# design.net
KiCad netlist of a schematic drawn in Altium Designer
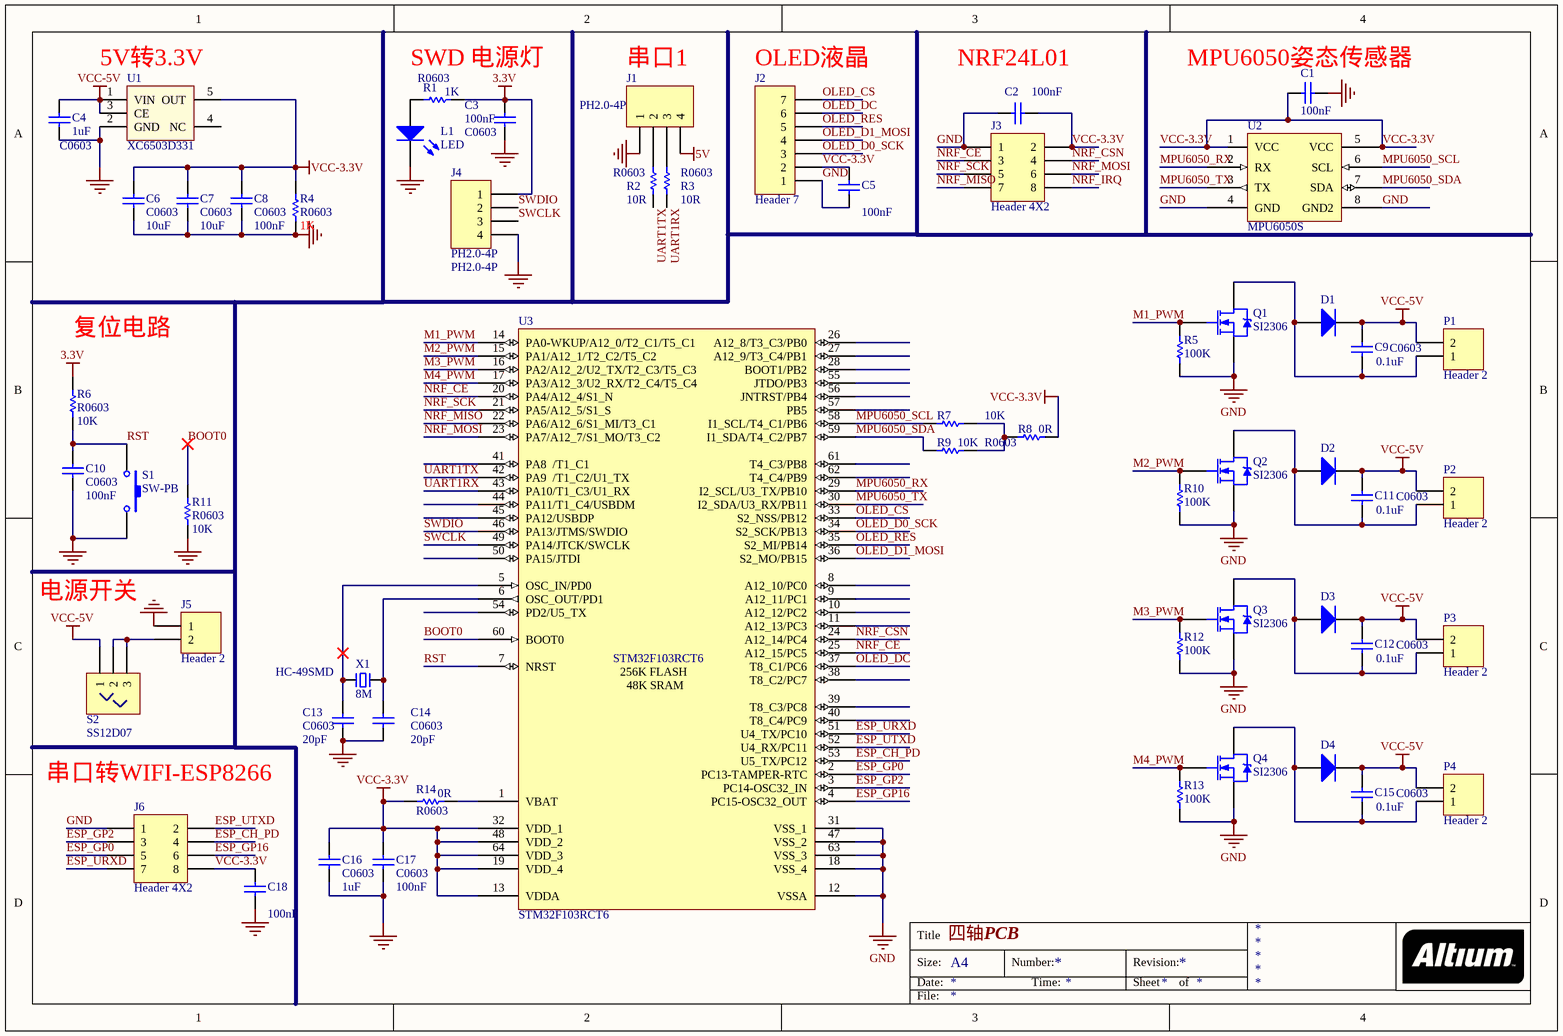
[diagram p0: 四轴.SchDoc]

(export (version "E")
  (design (tool "Eeschema 10.0.6"))
  (components
    (comp (ref "C1")
      (value "100nF")
      (footprint "LiyaoPCB库:0603")
      (description "Capacitor")
      (fields (field (name "Comment") "C0603") (field (name "PUBLISHER") "Altium Limited"))
      (libsource (lib "Miscellaneous Devices") (part "Cap"))
    )
    (comp (ref "C2")
      (value "100nF")
      (footprint "LiyaoPCB库:0603")
      (description "Capacitor")
      (fields (field (name "Comment") "C0603") (field (name "PUBLISHER") "Altium Limited"))
      (libsource (lib "Miscellaneous Devices") (part "Cap"))
    )
    (comp (ref "C3")
      (value "C0603")
      (footprint "0603")
      (description "Capacitor")
      (fields (field (name "ALTIUM_VALUE") "100nF") (field (name "PUBLISHER") "Altium Limited"))
      (libsource (lib "Miscellaneous Devices") (part "Cap"))
    )
    (comp (ref "C4")
      (value "C0603")
      (footprint "0603")
      (description "Capacitor")
      (fields (field (name "ALTIUM_VALUE") "1uF") (field (name "PUBLISHER") "Altium Limited"))
      (libsource (lib "Miscellaneous Devices") (part "Cap"))
    )
    (comp (ref "C5")
      (value "100nF")
      (footprint "LiyaoPCB库:0603")
      (description "Capacitor")
      (fields (field (name "Comment") "C0603") (field (name "PUBLISHER") "Altium Limited"))
      (libsource (lib "Miscellaneous Devices") (part "Cap"))
    )
    (comp (ref "C6")
      (value "C0603")
      (footprint "0603")
      (description "Capacitor")
      (fields (field (name "ALTIUM_VALUE") "10uF") (field (name "PUBLISHER") "Altium Limited"))
      (libsource (lib "Miscellaneous Devices") (part "Cap"))
    )
    (comp (ref "C7")
      (value "C0603")
      (footprint "0603")
      (description "Capacitor")
      (fields (field (name "ALTIUM_VALUE") "10uF") (field (name "PUBLISHER") "Altium Limited"))
      (libsource (lib "Miscellaneous Devices") (part "Cap"))
    )
    (comp (ref "C8")
      (value "C0603")
      (footprint "0603")
      (description "Capacitor")
      (fields (field (name "ALTIUM_VALUE") "100nF") (field (name "PUBLISHER") "Altium Limited"))
      (libsource (lib "Miscellaneous Devices") (part "Cap"))
    )
    (comp (ref "C9")
      (value "C0603")
      (footprint "0603")
      (description "Capacitor")
      (fields (field (name "ALTIUM_VALUE") "0.1uF") (field (name "PUBLISHER") "Altium Limited"))
      (libsource (lib "Miscellaneous Devices") (part "Cap"))
    )
    (comp (ref "C10")
      (value "C0603")
      (footprint "0603")
      (description "Capacitor")
      (fields (field (name "ALTIUM_VALUE") "100nF") (field (name "PUBLISHER") "Altium Limited"))
      (libsource (lib "Miscellaneous Devices") (part "Cap"))
    )
    (comp (ref "C11")
      (value "C0603")
      (footprint "0603")
      (description "Capacitor")
      (fields (field (name "ALTIUM_VALUE") "0.1uF") (field (name "PUBLISHER") "Altium Limited"))
      (libsource (lib "Miscellaneous Devices") (part "Cap"))
    )
    (comp (ref "C12")
      (value "C0603")
      (footprint "0603")
      (description "Capacitor")
      (fields (field (name "ALTIUM_VALUE") "0.1uF") (field (name "PUBLISHER") "Altium Limited"))
      (libsource (lib "Miscellaneous Devices") (part "Cap"))
    )
    (comp (ref "C13")
      (value "C0603")
      (footprint "0603")
      (description "Capacitor")
      (fields (field (name "ALTIUM_VALUE") "20pF") (field (name "PUBLISHER") "Altium Limited"))
      (libsource (lib "Miscellaneous Devices") (part "Cap"))
    )
    (comp (ref "C14")
      (value "C0603")
      (footprint "0603")
      (description "Capacitor")
      (fields (field (name "ALTIUM_VALUE") "20pF") (field (name "PUBLISHER") "Altium Limited"))
      (libsource (lib "Miscellaneous Devices") (part "Cap"))
    )
    (comp (ref "C15")
      (value "C0603")
      (footprint "0603")
      (description "Capacitor")
      (fields (field (name "ALTIUM_VALUE") "0.1uF") (field (name "PUBLISHER") "Altium Limited"))
      (libsource (lib "Miscellaneous Devices") (part "Cap"))
    )
    (comp (ref "C16")
      (value "C0603")
      (footprint "LiyaoPCB库:0603")
      (description "Capacitor")
      (fields (field (name "ALTIUM_VALUE") "1uF") (field (name "PUBLISHER") "Altium Limited"))
      (libsource (lib "Miscellaneous Devices") (part "Cap"))
    )
    (comp (ref "C17")
      (value "C0603")
      (footprint "LiyaoPCB库:0603")
      (description "Capacitor")
      (fields (field (name "ALTIUM_VALUE") "100nF") (field (name "PUBLISHER") "Altium Limited"))
      (libsource (lib "Miscellaneous Devices") (part "Cap"))
    )
    (comp (ref "C18")
      (value "100nF")
      (footprint "LiyaoPCB库:0603")
      (description "Capacitor")
      (fields (field (name "Comment") "C0603") (field (name "PUBLISHER") "Altium Limited"))
      (libsource (lib "Miscellaneous Devices") (part "Cap"))
    )
    (comp (ref "D1")
      (value "SS14")
      (footprint "LiyaoPCB库:SMA")
      (description "28V 1A")
      (fields (field (name "PUBLISHER") "Altium Limited"))
      (libsource (lib "Liyao原理图库") (part "SS14"))
    )
    (comp (ref "D2")
      (value "SS14")
      (footprint "LiyaoPCB库:SMA")
      (description "28V 1A")
      (fields (field (name "PUBLISHER") "Altium Limited"))
      (libsource (lib "Liyao原理图库") (part "SS14"))
    )
    (comp (ref "D3")
      (value "SS14")
      (footprint "LiyaoPCB库:SMA")
      (description "28V 1A")
      (fields (field (name "PUBLISHER") "Altium Limited"))
      (libsource (lib "Liyao原理图库") (part "SS14"))
    )
    (comp (ref "D4")
      (value "SS14")
      (footprint "LiyaoPCB库:SMA")
      (description "28V 1A")
      (fields (field (name "PUBLISHER") "Altium Limited"))
      (libsource (lib "Liyao原理图库") (part "SS14"))
    )
    (comp (ref "J1")
      (value "PH2.0-4P")
      (footprint "PH2.0-4P")
      (description "Header, 4-Pin")
      (fields (field (name "PUBLISHER") "Altium Limited"))
      (libsource (lib "Miscellaneous Connectors") (part "Header 4"))
    )
    (comp (ref "J2")
      (value "Header 7")
      (footprint "HDR1X7")
      (description "Header, 7-Pin")
      (fields (field (name "PUBLISHER") "Altium Limited"))
      (libsource (lib "Miscellaneous Connectors") (part "Header 7"))
    )
    (comp (ref "J3")
      (value "Header 4X2")
      (footprint "HDR2X4")
      (description "Header, 4-Pin, Dual row")
      (fields (field (name "PUBLISHER") "Altium Limited"))
      (libsource (lib "Miscellaneous Connectors") (part "Header 4X2"))
    )
    (comp (ref "J4")
      (value "PH2.0-4P")
      (footprint "PH2.0-4P")
      (description "Header, 4-Pin")
      (fields (field (name "ALTIUM_VALUE") "PH2.0-4P") (field (name "PUBLISHER") "Altium Limited"))
      (libsource (lib "") (part "Header 4_1"))
    )
    (comp (ref "J5")
      (value "Header 2")
      (footprint "XH2.54-2")
      (description "Header, 2-Pin")
      (fields (field (name "PUBLISHER") "Altium Limited"))
      (libsource (lib "") (part "Header 2_1"))
    )
    (comp (ref "J6")
      (value "Header 4X2")
      (footprint "HDR2X4")
      (description "Header, 4-Pin, Dual row")
      (fields (field (name "PUBLISHER") "Altium Limited"))
      (libsource (lib "Miscellaneous Connectors") (part "Header 4X2"))
    )
    (comp (ref "L1") (value "LED") (footprint "0603") (libsource (lib "Sparks") (part "LED")))
    (comp (ref "P1")
      (value "Header 2")
      (footprint "HDR1X2")
      (description "Header, 2-Pin")
      (fields (field (name "PUBLISHER") "Altium Limited"))
      (libsource (lib "Miscellaneous Connectors") (part "Header 2"))
    )
    (comp (ref "P2")
      (value "Header 2")
      (footprint "HDR1X2")
      (description "Header, 2-Pin")
      (fields (field (name "PUBLISHER") "Altium Limited"))
      (libsource (lib "Miscellaneous Connectors") (part "Header 2"))
    )
    (comp (ref "P3")
      (value "Header 2")
      (footprint "HDR1X2")
      (description "Header, 2-Pin")
      (fields (field (name "PUBLISHER") "Altium Limited"))
      (libsource (lib "Miscellaneous Connectors") (part "Header 2"))
    )
    (comp (ref "P4")
      (value "Header 2")
      (footprint "HDR1X2")
      (description "Header, 2-Pin")
      (fields (field (name "PUBLISHER") "Altium Limited"))
      (libsource (lib "Miscellaneous Connectors") (part "Header 2"))
    )
    (comp (ref "Q1")
      (value "SI2306")
      (footprint "LiyaoPCB库:SOT-23_L")
      (description "N-Channel MOSFET")
      (fields (field (name "PUBLISHER") "Altium Limited"))
      (libsource (lib "Liyao原理图库") (part "MOS-N"))
    )
    (comp (ref "Q2")
      (value "SI2306")
      (footprint "LiyaoPCB库:SOT-23_L")
      (description "N-Channel MOSFET")
      (fields (field (name "PUBLISHER") "Altium Limited"))
      (libsource (lib "Liyao原理图库") (part "MOS-N"))
    )
    (comp (ref "Q3")
      (value "SI2306")
      (footprint "LiyaoPCB库:SOT-23_L")
      (description "N-Channel MOSFET")
      (fields (field (name "PUBLISHER") "Altium Limited"))
      (libsource (lib "Liyao原理图库") (part "MOS-N"))
    )
    (comp (ref "Q4")
      (value "SI2306")
      (footprint "LiyaoPCB库:SOT-23_L")
      (description "N-Channel MOSFET")
      (fields (field (name "PUBLISHER") "Altium Limited"))
      (libsource (lib "Liyao原理图库") (part "MOS-N"))
    )
    (comp (ref "R1")
      (value "R0603")
      (footprint "0603")
      (description "Resistor")
      (fields (field (name "ALTIUM_VALUE") "1K") (field (name "PUBLISHER") "Altium Limited"))
      (libsource (lib "Miscellaneous Devices") (part "Res1"))
    )
    (comp (ref "R2")
      (value "R0603")
      (footprint "0603")
      (description "Resistor")
      (fields (field (name "ALTIUM_VALUE") "10R") (field (name "PUBLISHER") "Altium Limited"))
      (libsource (lib "Miscellaneous Devices") (part "Res1"))
    )
    (comp (ref "R3")
      (value "R0603")
      (footprint "0603")
      (description "Resistor")
      (fields (field (name "ALTIUM_VALUE") "10R") (field (name "PUBLISHER") "Altium Limited"))
      (libsource (lib "Miscellaneous Devices") (part "Res1"))
    )
    (comp (ref "R4")
      (value "R0603")
      (footprint "0603")
      (description "Resistor")
      (fields (field (name "ALTIUM_VALUE") "1K") (field (name "PUBLISHER") "Altium Limited"))
      (libsource (lib "Miscellaneous Devices") (part "Res1"))
    )
    (comp (ref "R5")
      (value "100K")
      (footprint "LiyaoPCB库:0603")
      (description "Resistor")
      (fields (field (name "Comment") "Res1") (field (name "PUBLISHER") "Altium Limited"))
      (libsource (lib "Miscellaneous Devices") (part "Res1"))
    )
    (comp (ref "R6")
      (value "R0603")
      (footprint "0603")
      (description "Resistor")
      (fields (field (name "ALTIUM_VALUE") "10K") (field (name "PUBLISHER") "Altium Limited"))
      (libsource (lib "Miscellaneous Devices") (part "Res1"))
    )
    (comp (ref "R7")
      (value "10K")
      (footprint "0603")
      (description "Resistor")
      (fields (field (name "PUBLISHER") "Altium Limited"))
      (libsource (lib "Miscellaneous Devices") (part "Res1"))
    )
    (comp (ref "R8")
      (value "0R")
      (footprint "0603")
      (description "Resistor")
      (fields (field (name "PUBLISHER") "Altium Limited"))
      (libsource (lib "Miscellaneous Devices") (part "Res1"))
    )
    (comp (ref "R9")
      (value "R0603")
      (footprint "0603")
      (description "Resistor")
      (fields (field (name "ALTIUM_VALUE") "10K") (field (name "PUBLISHER") "Altium Limited"))
      (libsource (lib "Miscellaneous Devices") (part "Res1"))
    )
    (comp (ref "R10")
      (value "100K")
      (footprint "LiyaoPCB库:0603")
      (description "Resistor")
      (fields (field (name "Comment") "Res1") (field (name "PUBLISHER") "Altium Limited"))
      (libsource (lib "Miscellaneous Devices") (part "Res1"))
    )
    (comp (ref "R11")
      (value "R0603")
      (footprint "0603")
      (description "Resistor")
      (fields (field (name "ALTIUM_VALUE") "10K") (field (name "PUBLISHER") "Altium Limited"))
      (libsource (lib "Miscellaneous Devices") (part "Res1"))
    )
    (comp (ref "R12")
      (value "100K")
      (footprint "LiyaoPCB库:0603")
      (description "Resistor")
      (fields (field (name "Comment") "Res1") (field (name "PUBLISHER") "Altium Limited"))
      (libsource (lib "Miscellaneous Devices") (part "Res1"))
    )
    (comp (ref "R13")
      (value "100K")
      (footprint "LiyaoPCB库:0603")
      (description "Resistor")
      (fields (field (name "Comment") "Res1") (field (name "PUBLISHER") "Altium Limited"))
      (libsource (lib "Miscellaneous Devices") (part "Res1"))
    )
    (comp (ref "R14")
      (value "R0603")
      (footprint "0603")
      (description "Resistor")
      (fields (field (name "ALTIUM_VALUE") "0R") (field (name "PUBLISHER") "Altium Limited"))
      (libsource (lib "Miscellaneous Devices") (part "Res1"))
    )
    (comp (ref "S1")
      (value "SW-PB")
      (footprint "SPST-2")
      (description "Switch")
      (fields (field (name "PUBLISHER") "Altium Limited"))
      (libsource (lib "Miscellaneous Devices") (part "SW-PB"))
    )
    (comp (ref "S2")
      (value "SS12D07")
      (footprint "LiyaoPCB库:SS-12D07")
      (libsource (lib "Liyao原理图库") (part "SS12D07"))
    )
    (comp (ref "U1")
      (value "XC6503D331")
      (footprint "SOT23-5")
      (libsource (lib "CYSchlib") (part "XC6503Dxxx"))
    )
    (comp (ref "U2")
      (value "MPU6050S")
      (footprint "LiyaoPCB库:MPU6050S")
      (libsource (lib "Liyao原理图库") (part "MPU6050S"))
    )
    (comp (ref "U3")
      (value "STM32F103RCT6")
      (footprint "LQFP64_N")
      (fields (field (name "PUBLISHER") "Altium Limited"))
      (libsource (lib "Liyao原理图库") (part "STM32F103RCT6"))
    )
    (comp (ref "X1")
      (value "8M")
      (footprint "HC-49SMD")
      (fields (field (name "ALTIUM_VALUE") "HC-49SMD"))
      (libsource (lib "CYSchlib") (part "XTAL"))
    )
  )
  (nets
    (net (code "1") (name "/BOOT0") (class "Default")
      (node (ref "R11") (pin "1") (pinfunction "1_1") (pintype "passive"))
      (node (ref "U3") (pin "60") (pinfunction "BOOT0_60") (pintype "input"))
    )
    (net (code "2") (name "/ESP_CH_PD") (class "Default")
      (node (ref "J6") (pin "4") (pinfunction "4_4") (pintype "passive"))
      (node (ref "U3") (pin "53") (pinfunction "U5_TX/PC12_53") (pintype "bidirectional"))
    )
    (net (code "3") (name "/ESP_GP0") (class "Default")
      (node (ref "J6") (pin "5") (pinfunction "5_5") (pintype "passive"))
      (node (ref "U3") (pin "2") (pinfunction "PC13-TAMPER-RTC_2") (pintype "bidirectional"))
    )
    (net (code "4") (name "/ESP_GP2") (class "Default")
      (node (ref "J6") (pin "3") (pinfunction "3_3") (pintype "passive"))
      (node (ref "U3") (pin "3") (pinfunction "PC14-OSC32_IN_3") (pintype "bidirectional"))
    )
    (net (code "5") (name "/ESP_GP16") (class "Default")
      (node (ref "J6") (pin "6") (pinfunction "6_6") (pintype "passive"))
      (node (ref "U3") (pin "4") (pinfunction "PC15-OSC32_OUT_4") (pintype "bidirectional"))
    )
    (net (code "6") (name "/ESP_URXD") (class "Default")
      (node (ref "J6") (pin "7") (pinfunction "7_7") (pintype "passive"))
      (node (ref "U3") (pin "51") (pinfunction "U4_TX/PC10_51") (pintype "bidirectional"))
    )
    (net (code "7") (name "/ESP_UTXD") (class "Default")
      (node (ref "J6") (pin "2") (pinfunction "2_2") (pintype "passive"))
      (node (ref "U3") (pin "52") (pinfunction "U4_RX/PC11_52") (pintype "bidirectional"))
    )
    (net (code "8") (name "/M1_PWM") (class "Default")
      (node (ref "Q1") (pin "1") (pinfunction "G_1") (pintype "passive"))
      (node (ref "R5") (pin "2") (pinfunction "2_2") (pintype "passive"))
      (node (ref "U3") (pin "14") (pinfunction "PA0-WKUP/A12_0/T2_C1/T5_C1_14") (pintype "bidirectional"))
    )
    (net (code "9") (name "/M2_PWM") (class "Default")
      (node (ref "Q2") (pin "1") (pinfunction "G_1") (pintype "passive"))
      (node (ref "R10") (pin "2") (pinfunction "2_2") (pintype "passive"))
      (node (ref "U3") (pin "15") (pinfunction "PA1/A12_1/T2_C2/T5_C2_15") (pintype "bidirectional"))
    )
    (net (code "10") (name "/M3_PWM") (class "Default")
      (node (ref "Q3") (pin "1") (pinfunction "G_1") (pintype "passive"))
      (node (ref "R12") (pin "2") (pinfunction "2_2") (pintype "passive"))
      (node (ref "U3") (pin "16") (pinfunction "PA2/A12_2/U2_TX/T2_C3/T5_C3_16") (pintype "bidirectional"))
    )
    (net (code "11") (name "/M4_PWM") (class "Default")
      (node (ref "Q4") (pin "1") (pinfunction "G_1") (pintype "passive"))
      (node (ref "R13") (pin "2") (pinfunction "2_2") (pintype "passive"))
      (node (ref "U3") (pin "17") (pinfunction "PA3/A12_3/U2_RX/T2_C4/T5_C4_17") (pintype "bidirectional"))
    )
    (net (code "12") (name "/MPU6050_RX") (class "Default")
      (node (ref "U2") (pin "2") (pinfunction "RX_2") (pintype "input"))
      (node (ref "U3") (pin "29") (pinfunction "I2_SCL/U3_TX/PB10_29") (pintype "bidirectional"))
    )
    (net (code "13") (name "/MPU6050_SCL") (class "Default")
      (node (ref "R7") (pin "1") (pinfunction "1_1") (pintype "passive"))
      (node (ref "U2") (pin "6") (pinfunction "SCL_6") (pintype "input"))
      (node (ref "U3") (pin "58") (pinfunction "I1_SCL/T4_C1/PB6_58") (pintype "bidirectional"))
    )
    (net (code "14") (name "/MPU6050_SDA") (class "Default")
      (node (ref "R9") (pin "1") (pinfunction "1_1") (pintype "passive"))
      (node (ref "U2") (pin "7") (pinfunction "SDA_7") (pintype "bidirectional"))
      (node (ref "U3") (pin "59") (pinfunction "I1_SDA/T4_C2/PB7_59") (pintype "bidirectional"))
    )
    (net (code "15") (name "/MPU6050_TX") (class "Default")
      (node (ref "U2") (pin "3") (pinfunction "TX_3") (pintype "output"))
      (node (ref "U3") (pin "30") (pinfunction "I2_SDA/U3_RX/PB11_30") (pintype "bidirectional"))
    )
    (net (code "16") (name "/NRF_CE") (class "Default")
      (node (ref "J3") (pin "3") (pinfunction "3_3") (pintype "passive"))
      (node (ref "U3") (pin "20") (pinfunction "PA4/A12_4/S1_N_20") (pintype "bidirectional"))
      (node (ref "U3") (pin "25") (pinfunction "A12_15/PC5_25") (pintype "bidirectional"))
    )
    (net (code "17") (name "/NRF_CSN") (class "Default")
      (node (ref "J3") (pin "4") (pinfunction "4_4") (pintype "passive"))
      (node (ref "U3") (pin "24") (pinfunction "A12_14/PC4_24") (pintype "bidirectional"))
    )
    (net (code "18") (name "/NRF_IRQ") (class "Default")
      (node (ref "J3") (pin "8") (pinfunction "8_8") (pintype "passive"))
    )
    (net (code "19") (name "/NRF_MISO") (class "Default")
      (node (ref "J3") (pin "7") (pinfunction "7_7") (pintype "passive"))
      (node (ref "U3") (pin "22") (pinfunction "PA6/A12_6/S1_MI/T3_C1_22") (pintype "bidirectional"))
    )
    (net (code "20") (name "/NRF_MOSI") (class "Default")
      (node (ref "J3") (pin "6") (pinfunction "6_6") (pintype "passive"))
      (node (ref "U3") (pin "23") (pinfunction "PA7/A12_7/S1_MO/T3_C2_23") (pintype "bidirectional"))
    )
    (net (code "21") (name "/NRF_SCK") (class "Default")
      (node (ref "J3") (pin "5") (pinfunction "5_5") (pintype "passive"))
      (node (ref "U3") (pin "21") (pinfunction "PA5/A12_5/S1_S_21") (pintype "bidirectional"))
    )
    (net (code "22") (name "/OLED_CS") (class "Default")
      (node (ref "J2") (pin "7") (pinfunction "7_7") (pintype "passive"))
      (node (ref "U3") (pin "33") (pinfunction "S2_NSS/PB12_33") (pintype "bidirectional"))
    )
    (net (code "23") (name "/OLED_D0_SCK") (class "Default")
      (node (ref "J2") (pin "3") (pinfunction "3_3") (pintype "passive"))
      (node (ref "U3") (pin "34") (pinfunction "S2_SCK/PB13_34") (pintype "bidirectional"))
    )
    (net (code "24") (name "/OLED_D1_MOSI") (class "Default")
      (node (ref "J2") (pin "4") (pinfunction "4_4") (pintype "passive"))
      (node (ref "U3") (pin "36") (pinfunction "S2_MO/PB15_36") (pintype "bidirectional"))
    )
    (net (code "25") (name "/OLED_DC") (class "Default")
      (node (ref "J2") (pin "6") (pinfunction "6_6") (pintype "passive"))
      (node (ref "U3") (pin "37") (pinfunction "T8_C1/PC6_37") (pintype "bidirectional"))
    )
    (net (code "26") (name "/OLED_RES") (class "Default")
      (node (ref "J2") (pin "5") (pinfunction "5_5") (pintype "passive"))
      (node (ref "U3") (pin "35") (pinfunction "S2_MI/PB14_35") (pintype "bidirectional"))
    )
    (net (code "27") (name "/RST") (class "Default")
      (node (ref "C10") (pin "1") (pinfunction "1_1") (pintype "passive"))
      (node (ref "R6") (pin "2") (pinfunction "2_2") (pintype "passive"))
      (node (ref "S1") (pin "1") (pinfunction "1_1") (pintype "passive"))
      (node (ref "U3") (pin "7") (pinfunction "NRST_7") (pintype "bidirectional"))
    )
    (net (code "28") (name "/SWCLK") (class "Default")
      (node (ref "J4") (pin "3") (pinfunction "3_3") (pintype "passive"))
      (node (ref "U3") (pin "49") (pinfunction "PA14/JTCK/SWCLK_49") (pintype "bidirectional"))
    )
    (net (code "29") (name "/SWDIO") (class "Default")
      (node (ref "J4") (pin "2") (pinfunction "2_2") (pintype "passive"))
      (node (ref "U3") (pin "46") (pinfunction "PA13/JTMS/SWDIO_46") (pintype "bidirectional"))
    )
    (net (code "30") (name "/UART1RX") (class "Default")
      (node (ref "R3") (pin "2") (pinfunction "2_2") (pintype "passive"))
      (node (ref "U3") (pin "43") (pinfunction "PA10/T1_C3/U1_RX_43") (pintype "bidirectional"))
    )
    (net (code "31") (name "/UART1TX") (class "Default")
      (node (ref "R2") (pin "2") (pinfunction "2_2") (pintype "passive"))
      (node (ref "U3") (pin "42") (pinfunction "PA9__/T1_C2/U1_TX_42") (pintype "bidirectional"))
    )
    (net (code "32") (name "3.3V") (class "Default")
      (node (ref "C3") (pin "1") (pinfunction "1_1") (pintype "passive"))
      (node (ref "J4") (pin "1") (pinfunction "1_1") (pintype "passive"))
      (node (ref "R1") (pin "2") (pinfunction "2_2") (pintype "passive"))
      (node (ref "R6") (pin "1") (pinfunction "1_1") (pintype "passive"))
    )
    (net (code "33") (name "5V") (class "Default")
      (node (ref "J1") (pin "4") (pinfunction "4_4") (pintype "passive"))
    )
    (net (code "34") (name "GND") (class "Default")
      (node (ref "C1") (pin "2") (pinfunction "2_2") (pintype "passive"))
      (node (ref "C10") (pin "2") (pinfunction "2_2") (pintype "passive"))
      (node (ref "C13") (pin "1") (pinfunction "1_1") (pintype "passive"))
      (node (ref "C14") (pin "1") (pinfunction "1_1") (pintype "passive"))
      (node (ref "C16") (pin "1") (pinfunction "1_1") (pintype "passive"))
      (node (ref "C17") (pin "1") (pinfunction "1_1") (pintype "passive"))
      (node (ref "C18") (pin "2") (pinfunction "2_2") (pintype "passive"))
      (node (ref "C2") (pin "2") (pinfunction "2_2") (pintype "passive"))
      (node (ref "C3") (pin "2") (pinfunction "2_2") (pintype "passive"))
      (node (ref "C4") (pin "1") (pinfunction "1_1") (pintype "passive"))
      (node (ref "C5") (pin "2") (pinfunction "2_2") (pintype "passive"))
      (node (ref "C6") (pin "2") (pinfunction "2_2") (pintype "passive"))
      (node (ref "C7") (pin "1") (pinfunction "1_1") (pintype "passive"))
      (node (ref "C8") (pin "1") (pinfunction "1_1") (pintype "passive"))
      (node (ref "J1") (pin "1") (pinfunction "1_1") (pintype "passive"))
      (node (ref "J2") (pin "1") (pinfunction "1_1") (pintype "passive"))
      (node (ref "J3") (pin "1") (pinfunction "1_1") (pintype "passive"))
      (node (ref "J4") (pin "4") (pinfunction "4_4") (pintype "passive"))
      (node (ref "J5") (pin "1") (pinfunction "1_1") (pintype "passive"))
      (node (ref "J6") (pin "1") (pinfunction "1_1") (pintype "passive"))
      (node (ref "L1") (pin "2") (pinfunction "K_2") (pintype "passive"))
      (node (ref "Q1") (pin "2") (pinfunction "S_2") (pintype "passive"))
      (node (ref "Q2") (pin "2") (pinfunction "S_2") (pintype "passive"))
      (node (ref "Q3") (pin "2") (pinfunction "S_2") (pintype "passive"))
      (node (ref "Q4") (pin "2") (pinfunction "S_2") (pintype "passive"))
      (node (ref "R10") (pin "1") (pinfunction "1_1") (pintype "passive"))
      (node (ref "R11") (pin "2") (pinfunction "2_2") (pintype "passive"))
      (node (ref "R12") (pin "1") (pinfunction "1_1") (pintype "passive"))
      (node (ref "R13") (pin "1") (pinfunction "1_1") (pintype "passive"))
      (node (ref "R4") (pin "1") (pinfunction "1_1") (pintype "passive"))
      (node (ref "R5") (pin "1") (pinfunction "1_1") (pintype "passive"))
      (node (ref "S1") (pin "2") (pinfunction "2_2") (pintype "passive"))
      (node (ref "U1") (pin "2") (pinfunction "GND_2") (pintype "passive"))
      (node (ref "U2") (pin "4") (pinfunction "GND_4") (pintype "power_in"))
      (node (ref "U2") (pin "8") (pinfunction "GND2_8") (pintype "passive"))
      (node (ref "U3") (pin "12") (pinfunction "VSSA_12") (pintype "power_in"))
      (node (ref "U3") (pin "18") (pinfunction "VSS_4_18") (pintype "power_in"))
      (node (ref "U3") (pin "31") (pinfunction "VSS_1_31") (pintype "power_in"))
      (node (ref "U3") (pin "47") (pinfunction "VSS_2_47") (pintype "power_in"))
      (node (ref "U3") (pin "63") (pinfunction "VSS_3_63") (pintype "power_in"))
    )
    (net (code "35") (name "Net-(D1-A)") (class "Default")
      (node (ref "C9") (pin "1") (pinfunction "1_1") (pintype "passive"))
      (node (ref "D1") (pin "1") (pinfunction "A_1") (pintype "passive"))
      (node (ref "P1") (pin "1") (pinfunction "1_1") (pintype "passive"))
      (node (ref "Q1") (pin "3") (pinfunction "D_3") (pintype "passive"))
    )
    (net (code "36") (name "Net-(D2-A)") (class "Default")
      (node (ref "C11") (pin "1") (pinfunction "1_1") (pintype "passive"))
      (node (ref "D2") (pin "1") (pinfunction "A_1") (pintype "passive"))
      (node (ref "P2") (pin "1") (pinfunction "1_1") (pintype "passive"))
      (node (ref "Q2") (pin "3") (pinfunction "D_3") (pintype "passive"))
    )
    (net (code "37") (name "Net-(D3-A)") (class "Default")
      (node (ref "C12") (pin "1") (pinfunction "1_1") (pintype "passive"))
      (node (ref "D3") (pin "1") (pinfunction "A_1") (pintype "passive"))
      (node (ref "P3") (pin "1") (pinfunction "1_1") (pintype "passive"))
      (node (ref "Q3") (pin "3") (pinfunction "D_3") (pintype "passive"))
    )
    (net (code "38") (name "Net-(D4-A)") (class "Default")
      (node (ref "C15") (pin "1") (pinfunction "1_1") (pintype "passive"))
      (node (ref "D4") (pin "1") (pinfunction "A_1") (pintype "passive"))
      (node (ref "P4") (pin "1") (pinfunction "1_1") (pintype "passive"))
      (node (ref "Q4") (pin "3") (pinfunction "D_3") (pintype "passive"))
    )
    (net (code "39") (name "Net-(J1-Pad2)") (class "Default")
      (node (ref "J1") (pin "2") (pinfunction "2_2") (pintype "passive"))
      (node (ref "R2") (pin "1") (pinfunction "1_1") (pintype "passive"))
    )
    (net (code "40") (name "Net-(J1-Pad3)") (class "Default")
      (node (ref "J1") (pin "3") (pinfunction "3_3") (pintype "passive"))
      (node (ref "R3") (pin "1") (pinfunction "1_1") (pintype "passive"))
    )
    (net (code "41") (name "Net-(J5-Pad2)") (class "Default")
      (node (ref "J5") (pin "2") (pinfunction "2_2") (pintype "passive"))
      (node (ref "S2") (pin "2") (pinfunction "2_2") (pintype "passive"))
      (node (ref "S2") (pin "3") (pinfunction "3_3") (pintype "passive"))
    )
    (net (code "42") (name "Net-(L1-A)") (class "Default")
      (node (ref "L1") (pin "1") (pinfunction "A_1") (pintype "passive"))
      (node (ref "R1") (pin "1") (pinfunction "1_1") (pintype "passive"))
    )
    (net (code "43") (name "Net-(R7-Pad2)") (class "Default")
      (node (ref "R7") (pin "2") (pinfunction "2_2") (pintype "passive"))
      (node (ref "R8") (pin "2") (pinfunction "2_2") (pintype "passive"))
      (node (ref "R9") (pin "2") (pinfunction "2_2") (pintype "passive"))
    )
    (net (code "44") (name "Net-(U3-OSC_IN{slash}PD0)") (class "Default")
      (node (ref "C13") (pin "2") (pinfunction "2_2") (pintype "passive"))
      (node (ref "U3") (pin "5") (pinfunction "OSC_IN/PD0_5") (pintype "input"))
      (node (ref "X1") (pin "2") (pinfunction "2_2") (pintype "passive"))
    )
    (net (code "45") (name "Net-(U3-OSC_OUT{slash}PD1)") (class "Default")
      (node (ref "C14") (pin "2") (pinfunction "2_2") (pintype "passive"))
      (node (ref "U3") (pin "6") (pinfunction "OSC_OUT/PD1_6") (pintype "output"))
      (node (ref "X1") (pin "1") (pinfunction "1_1") (pintype "passive"))
    )
    (net (code "46") (name "Net-(U3-VBAT)") (class "Default")
      (node (ref "R14") (pin "2") (pinfunction "2_2") (pintype "passive"))
      (node (ref "U3") (pin "1") (pinfunction "VBAT_1") (pintype "power_in"))
    )
    (net (code "47") (name "VCC-3.3V") (class "Default")
      (node (ref "C1") (pin "1") (pinfunction "1_1") (pintype "passive"))
      (node (ref "C16") (pin "2") (pinfunction "2_2") (pintype "passive"))
      (node (ref "C17") (pin "2") (pinfunction "2_2") (pintype "passive"))
      (node (ref "C18") (pin "1") (pinfunction "1_1") (pintype "passive"))
      (node (ref "C2") (pin "1") (pinfunction "1_1") (pintype "passive"))
      (node (ref "C5") (pin "1") (pinfunction "1_1") (pintype "passive"))
      (node (ref "C6") (pin "1") (pinfunction "1_1") (pintype "passive"))
      (node (ref "C7") (pin "2") (pinfunction "2_2") (pintype "passive"))
      (node (ref "C8") (pin "2") (pinfunction "2_2") (pintype "passive"))
      (node (ref "J2") (pin "2") (pinfunction "2_2") (pintype "passive"))
      (node (ref "J3") (pin "2") (pinfunction "2_2") (pintype "passive"))
      (node (ref "J6") (pin "8") (pinfunction "8_8") (pintype "passive"))
      (node (ref "R14") (pin "1") (pinfunction "1_1") (pintype "passive"))
      (node (ref "R4") (pin "2") (pinfunction "2_2") (pintype "passive"))
      (node (ref "R8") (pin "1") (pinfunction "1_1") (pintype "passive"))
      (node (ref "U1") (pin "5") (pinfunction "OUT_5") (pintype "passive"))
      (node (ref "U2") (pin "1") (pinfunction "VCC_1") (pintype "power_in"))
      (node (ref "U2") (pin "5") (pinfunction "VCC_5") (pintype "power_in"))
      (node (ref "U3") (pin "13") (pinfunction "VDDA_13") (pintype "power_in"))
      (node (ref "U3") (pin "19") (pinfunction "VDD_4_19") (pintype "power_in"))
      (node (ref "U3") (pin "32") (pinfunction "VDD_1_32") (pintype "power_in"))
      (node (ref "U3") (pin "48") (pinfunction "VDD_2_48") (pintype "power_in"))
      (node (ref "U3") (pin "64") (pinfunction "VDD_3_64") (pintype "power_in"))
    )
    (net (code "48") (name "VCC-5V") (class "Default")
      (node (ref "C11") (pin "2") (pinfunction "2_2") (pintype "passive"))
      (node (ref "C12") (pin "2") (pinfunction "2_2") (pintype "passive"))
      (node (ref "C15") (pin "2") (pinfunction "2_2") (pintype "passive"))
      (node (ref "C4") (pin "2") (pinfunction "2_2") (pintype "passive"))
      (node (ref "C9") (pin "2") (pinfunction "2_2") (pintype "passive"))
      (node (ref "D1") (pin "2") (pinfunction "K_2") (pintype "passive"))
      (node (ref "D2") (pin "2") (pinfunction "K_2") (pintype "passive"))
      (node (ref "D3") (pin "2") (pinfunction "K_2") (pintype "passive"))
      (node (ref "D4") (pin "2") (pinfunction "K_2") (pintype "passive"))
      (node (ref "P1") (pin "2") (pinfunction "2_2") (pintype "passive"))
      (node (ref "P2") (pin "2") (pinfunction "2_2") (pintype "passive"))
      (node (ref "P3") (pin "2") (pinfunction "2_2") (pintype "passive"))
      (node (ref "P4") (pin "2") (pinfunction "2_2") (pintype "passive"))
      (node (ref "S2") (pin "1") (pinfunction "1_1") (pintype "passive"))
      (node (ref "U1") (pin "1") (pinfunction "VIN_1") (pintype "passive"))
      (node (ref "U1") (pin "3") (pinfunction "CE_3") (pintype "passive"))
    )
    (net (code "49") (name "unconnected-(U1-NC-Pad4)") (class "Default")
      (node (ref "U1") (pin "4") (pinfunction "NC_4") (pintype "passive"))
    )
    (net (code "50") (name "unconnected-(U3-A12_8{slash}T3_C3{slash}PB0-Pad26)") (class "Default")
      (node (ref "U3") (pin "26") (pinfunction "A12_8/T3_C3/PB0_26") (pintype "bidirectional"))
    )
    (net (code "51") (name "unconnected-(U3-A12_9{slash}T3_C4{slash}PB1-Pad27)") (class "Default")
      (node (ref "U3") (pin "27") (pinfunction "A12_9/T3_C4/PB1_27") (pintype "bidirectional"))
    )
    (net (code "52") (name "unconnected-(U3-A12_10{slash}PC0-Pad8)") (class "Default")
      (node (ref "U3") (pin "8") (pinfunction "A12_10/PC0_8") (pintype "bidirectional"))
    )
    (net (code "53") (name "unconnected-(U3-A12_11{slash}PC1-Pad9)") (class "Default")
      (node (ref "U3") (pin "9") (pinfunction "A12_11/PC1_9") (pintype "bidirectional"))
    )
    (net (code "54") (name "unconnected-(U3-A12_12{slash}PC2-Pad10)") (class "Default")
      (node (ref "U3") (pin "10") (pinfunction "A12_12/PC2_10") (pintype "bidirectional"))
    )
    (net (code "55") (name "unconnected-(U3-A12_13{slash}PC3-Pad11)") (class "Default")
      (node (ref "U3") (pin "11") (pinfunction "A12_13/PC3_11") (pintype "bidirectional"))
    )
    (net (code "56") (name "unconnected-(U3-BOOT1{slash}PB2-Pad28)") (class "Default")
      (node (ref "U3") (pin "28") (pinfunction "BOOT1/PB2_28") (pintype "bidirectional"))
    )
    (net (code "57") (name "unconnected-(U3-JNTRST{slash}PB4-Pad56)") (class "Default")
      (node (ref "U3") (pin "56") (pinfunction "JNTRST/PB4_56") (pintype "bidirectional"))
    )
    (net (code "58") (name "unconnected-(U3-JTDO{slash}PB3-Pad55)") (class "Default")
      (node (ref "U3") (pin "55") (pinfunction "JTDO/PB3_55") (pintype "bidirectional"))
    )
    (net (code "59") (name "unconnected-(U3-PA8__{slash}T1_C1-Pad41)") (class "Default")
      (node (ref "U3") (pin "41") (pinfunction "PA8__/T1_C1_41") (pintype "bidirectional"))
    )
    (net (code "60") (name "unconnected-(U3-PA11{slash}T1_C4{slash}USBDM-Pad44)") (class "Default")
      (node (ref "U3") (pin "44") (pinfunction "PA11/T1_C4/USBDM_44") (pintype "bidirectional"))
    )
    (net (code "61") (name "unconnected-(U3-PA12{slash}USBDP-Pad45)") (class "Default")
      (node (ref "U3") (pin "45") (pinfunction "PA12/USBDP_45") (pintype "bidirectional"))
    )
    (net (code "62") (name "unconnected-(U3-PA15{slash}JTDI-Pad50)") (class "Default")
      (node (ref "U3") (pin "50") (pinfunction "PA15/JTDI_50") (pintype "bidirectional"))
    )
    (net (code "63") (name "unconnected-(U3-PB5-Pad57)") (class "Default")
      (node (ref "U3") (pin "57") (pinfunction "PB5_57") (pintype "bidirectional"))
    )
    (net (code "64") (name "unconnected-(U3-PD2{slash}U5_TX-Pad54)") (class "Default")
      (node (ref "U3") (pin "54") (pinfunction "PD2/U5_TX_54") (pintype "bidirectional"))
    )
    (net (code "65") (name "unconnected-(U3-T4_C3{slash}PB8-Pad61)") (class "Default")
      (node (ref "U3") (pin "61") (pinfunction "T4_C3/PB8_61") (pintype "bidirectional"))
    )
    (net (code "66") (name "unconnected-(U3-T4_C4{slash}PB9-Pad62)") (class "Default")
      (node (ref "U3") (pin "62") (pinfunction "T4_C4/PB9_62") (pintype "bidirectional"))
    )
    (net (code "67") (name "unconnected-(U3-T8_C2{slash}PC7-Pad38)") (class "Default")
      (node (ref "U3") (pin "38") (pinfunction "T8_C2/PC7_38") (pintype "bidirectional"))
    )
    (net (code "68") (name "unconnected-(U3-T8_C3{slash}PC8-Pad39)") (class "Default")
      (node (ref "U3") (pin "39") (pinfunction "T8_C3/PC8_39") (pintype "bidirectional"))
    )
    (net (code "69") (name "unconnected-(U3-T8_C4{slash}PC9-Pad40)") (class "Default")
      (node (ref "U3") (pin "40") (pinfunction "T8_C4/PC9_40") (pintype "bidirectional"))
    )
  )
)
